# untitled.net
KiCad netlist of a schematic drawn in EAGLE
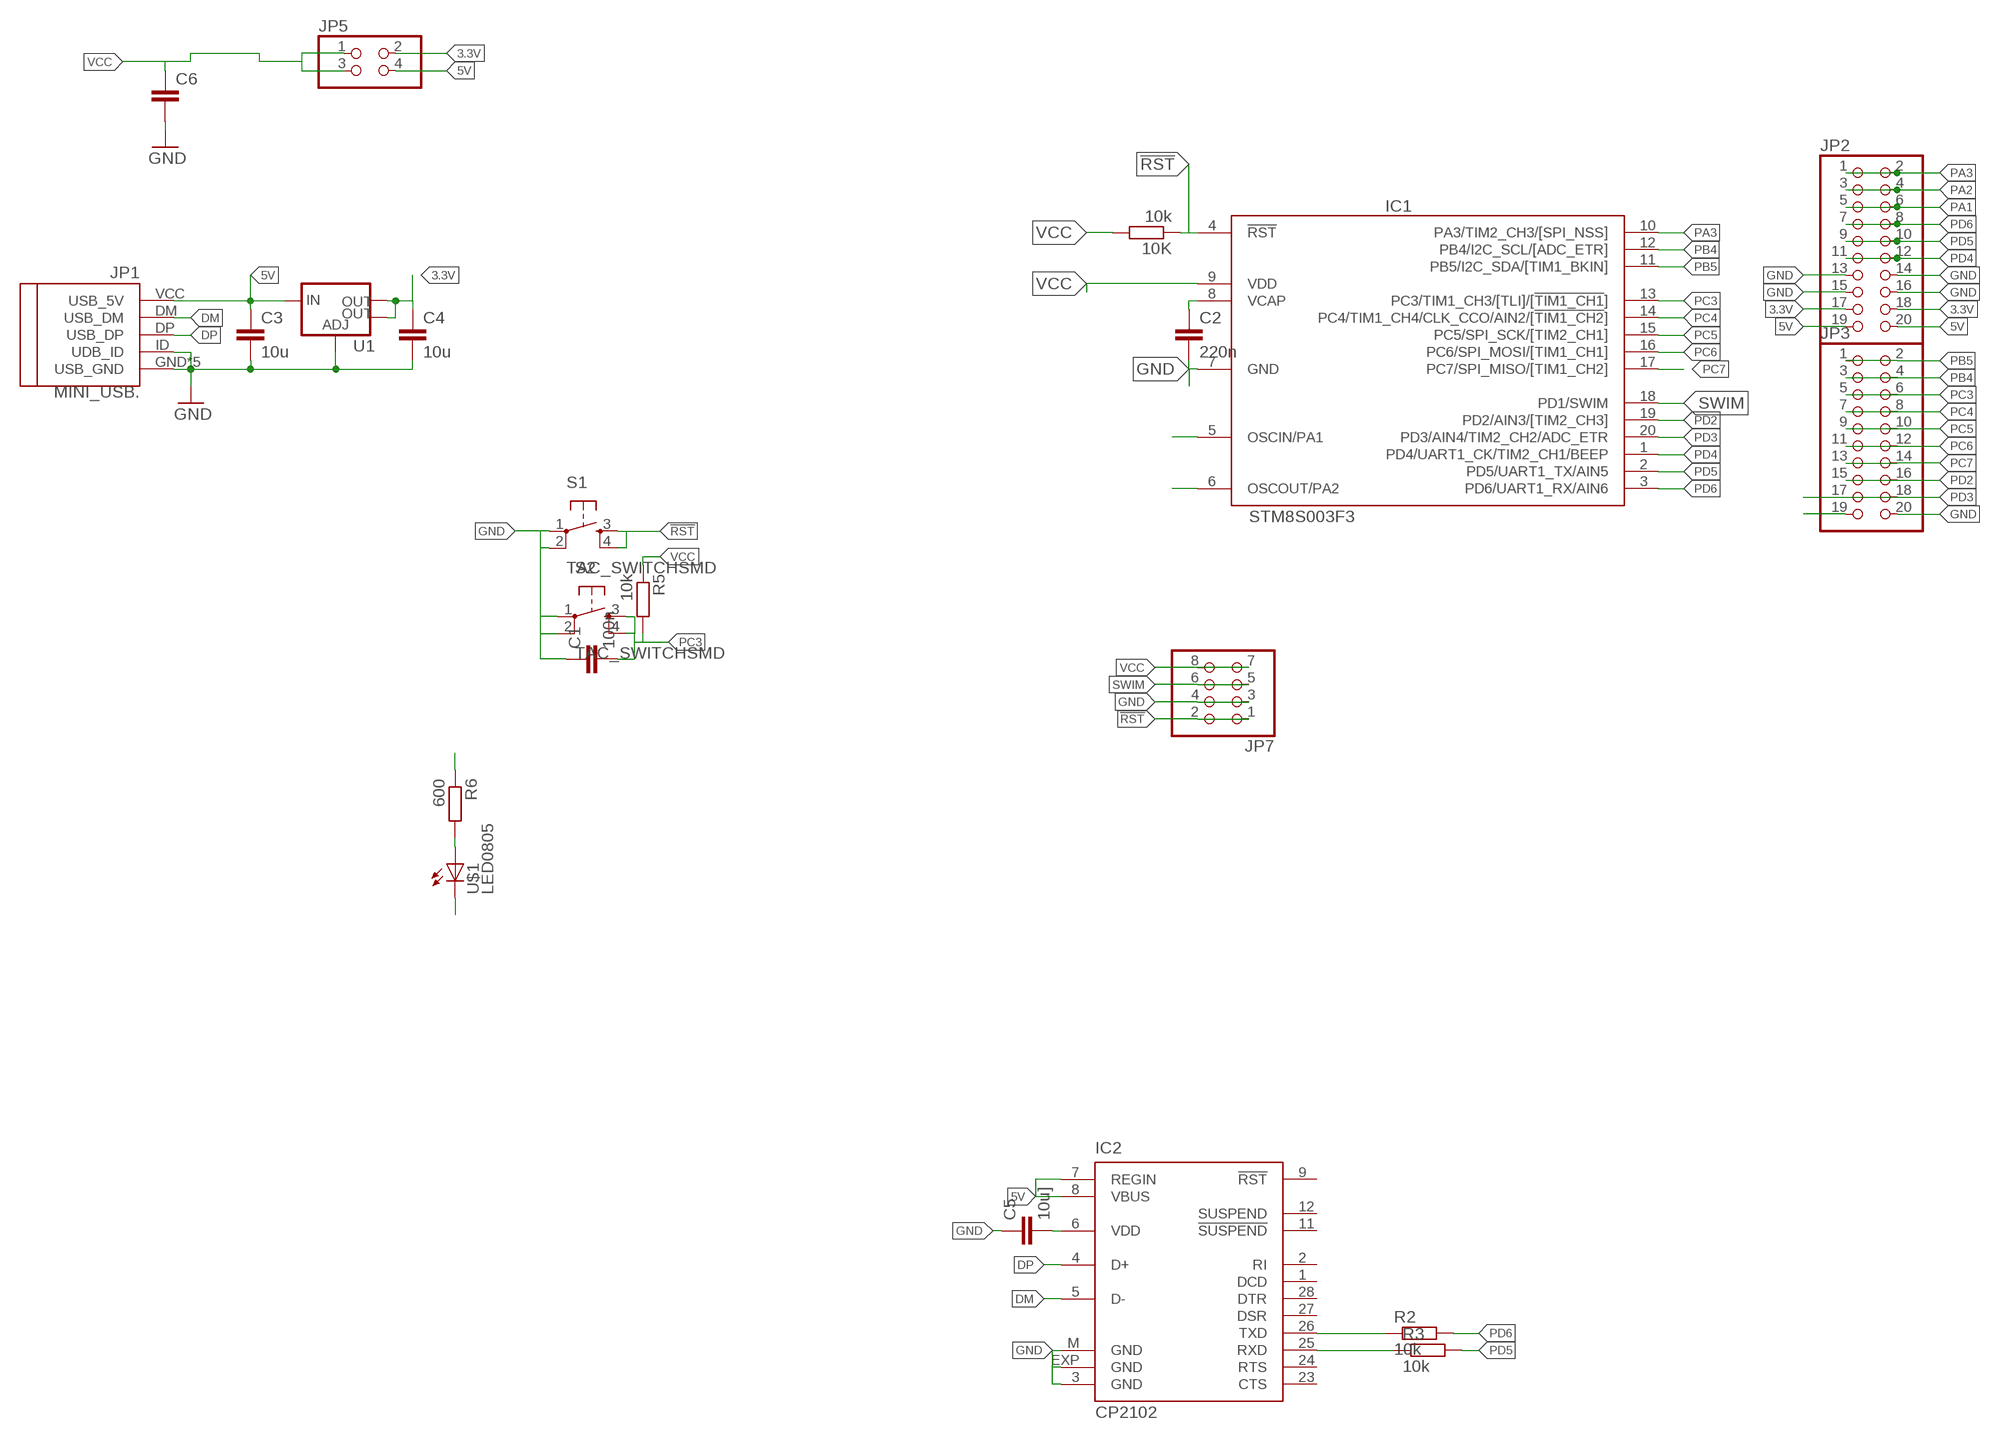
[diagram p0: schematic, sheet 1]

(export (version "E")
  (design (tool "Eeschema 10.0.6"))
  (components
    (comp (ref "10K")
      (value "10k")
      (footprint "eagle-import:0603")
      (libsource (lib "eagle-import") (part "R0603"))
    )
    (comp (ref "C1")
      (value "100n")
      (footprint "eagle-import:C0805")
      (libsource (lib "eagle-import") (part "CC0805"))
    )
    (comp (ref "C2")
      (value "220n")
      (footprint "eagle-import:C0603")
      (libsource (lib "eagle-import") (part "CC0603"))
    )
    (comp (ref "C3")
      (value "10u")
      (footprint "eagle-import:C0805")
      (libsource (lib "eagle-import") (part "CC0805"))
    )
    (comp (ref "C4")
      (value "10u")
      (footprint "eagle-import:C0805")
      (libsource (lib "eagle-import") (part "CC0805"))
    )
    (comp (ref "C5")
      (value "10u]")
      (footprint "eagle-import:C0603")
      (libsource (lib "eagle-import") (part "CC0603"))
    )
    (comp (ref "C6")
      (value "CC0805")
      (footprint "eagle-import:C0805")
      (libsource (lib "eagle-import") (part "CC0805"))
    )
    (comp (ref "IC1")
      (value "STM8S003F3")
      (footprint "eagle-import:TSSOP20")
      (libsource (lib "eagle-import") (part "STM8S003F3"))
    )
    (comp (ref "IC2")
      (value "CP2102")
      (footprint "eagle-import:MLP28")
      (fields (field (name "MF") "FARNELL") (field (name "MPN") "CP2102-GM"))
      (libsource (lib "eagle-import") (part "CP2102"))
    )
    (comp (ref "JP1")
      (value "MINI_USB.")
      (footprint "eagle-import:32005-201")
      (libsource (lib "eagle-import") (part "MINI_USB."))
    )
    (comp (ref "JP2")
      (value "PINHD-2X10_2.54-SMD")
      (footprint "eagle-import:2X10SMD")
      (libsource (lib "eagle-import") (part "PINHD-2X10_2.54-SMD"))
    )
    (comp (ref "JP3")
      (value "PINHD-2X10_2.54-SMD")
      (footprint "eagle-import:2X10SMD")
      (libsource (lib "eagle-import") (part "PINHD-2X10_2.54-SMD"))
    )
    (comp (ref "JP5")
      (value "PINHD-2X02_2.54-SMD")
      (footprint "eagle-import:2X02SMD")
      (libsource (lib "eagle-import") (part "PINHD-2X02_2.54-SMD"))
    )
    (comp (ref "JP7")
      (value "PINHD-2X04_2.54-SMD")
      (footprint "eagle-import:2X04SMD")
      (libsource (lib "eagle-import") (part "PINHD-2X04_2.54-SMD"))
    )
    (comp (ref "R2")
      (value "10k")
      (footprint "eagle-import:0603")
      (libsource (lib "eagle-import") (part "R0603"))
    )
    (comp (ref "R3")
      (value "10k")
      (footprint "eagle-import:0603")
      (libsource (lib "eagle-import") (part "R0603"))
    )
    (comp (ref "R5")
      (value "10k")
      (footprint "eagle-import:0603")
      (libsource (lib "eagle-import") (part "R0603"))
    )
    (comp (ref "R6")
      (value "600")
      (footprint "eagle-import:0603")
      (libsource (lib "eagle-import") (part "R0603"))
    )
    (comp (ref "S1")
      (value "TAC_SWITCHSMD")
      (footprint "eagle-import:TACTILE-SWITCH-SMD")
      (libsource (lib "eagle-import") (part "TAC_SWITCHSMD"))
    )
    (comp (ref "S2")
      (value "TAC_SWITCHSMD")
      (footprint "eagle-import:TACTILE-SWITCH-SMD")
      (libsource (lib "eagle-import") (part "TAC_SWITCHSMD"))
    )
    (comp (ref "U$1")
      (value "LED0805")
      (footprint "eagle-import:0805-LED")
      (libsource (lib "eagle-import") (part "LED0805"))
    )
    (comp (ref "U1")
      (value "V_REG_LM1117SOT223")
      (footprint "eagle-import:SOT223")
      (libsource (lib "eagle-import") (part "V_REG_LM1117SOT223"))
    )
  )
  (nets
    (net (code "1") (name "/~{RST}") (class "Default")
      (node (ref "10K") (pin "1") (pinfunction "1_1") (pintype "passive"))
      (node (ref "IC1") (pin "4") (pinfunction "~{RST}_4") (pintype "input"))
      (node (ref "JP7") (pin "1") (pinfunction "1_1") (pintype "passive"))
      (node (ref "JP7") (pin "2") (pinfunction "2_2") (pintype "passive"))
      (node (ref "S1") (pin "3") (pinfunction "3_3") (pintype "passive"))
      (node (ref "S1") (pin "4") (pinfunction "4_4") (pintype "passive"))
    )
    (net (code "2") (name "3.3V") (class "Default")
      (node (ref "C4") (pin "1") (pinfunction "1_1") (pintype "passive"))
      (node (ref "JP2") (pin "17") (pinfunction "17_17") (pintype "passive"))
      (node (ref "JP2") (pin "18") (pinfunction "18_18") (pintype "passive"))
      (node (ref "JP5") (pin "2") (pinfunction "2_2") (pintype "passive"))
      (node (ref "U1") (pin "2") (pinfunction "OUT_2") (pintype "output"))
      (node (ref "U1") (pin "4") (pinfunction "OUT_4") (pintype "output"))
    )
    (net (code "3") (name "5V") (class "Default")
      (node (ref "C3") (pin "1") (pinfunction "1_1") (pintype "passive"))
      (node (ref "IC2") (pin "7") (pinfunction "REGIN_7") (pintype "passive"))
      (node (ref "IC2") (pin "8") (pinfunction "VBUS_8") (pintype "input"))
      (node (ref "JP1") (pin "VCC") (pinfunction "USB_5V_VCC") (pintype "power_in"))
      (node (ref "JP2") (pin "19") (pinfunction "19_19") (pintype "passive"))
      (node (ref "JP2") (pin "20") (pinfunction "20_20") (pintype "passive"))
      (node (ref "JP5") (pin "4") (pinfunction "4_4") (pintype "passive"))
      (node (ref "U1") (pin "3") (pinfunction "IN_3") (pintype "input"))
    )
    (net (code "4") (name "DM") (class "Default")
      (node (ref "IC2") (pin "5") (pinfunction "D-_5") (pintype "bidirectional"))
      (node (ref "JP1") (pin "DM") (pinfunction "USB_DM_DM") (pintype "bidirectional"))
    )
    (net (code "5") (name "DP") (class "Default")
      (node (ref "IC2") (pin "4") (pinfunction "D+_4") (pintype "bidirectional"))
      (node (ref "JP1") (pin "DP") (pinfunction "USB_DP_DP") (pintype "bidirectional"))
    )
    (net (code "6") (name "GND") (class "Default")
      (node (ref "C1") (pin "1") (pinfunction "1_1") (pintype "passive"))
      (node (ref "C2") (pin "2") (pinfunction "2_2") (pintype "passive"))
      (node (ref "C3") (pin "2") (pinfunction "2_2") (pintype "passive"))
      (node (ref "C4") (pin "2") (pinfunction "2_2") (pintype "passive"))
      (node (ref "C5") (pin "1") (pinfunction "1_1") (pintype "passive"))
      (node (ref "C6") (pin "2") (pinfunction "2_2") (pintype "passive"))
      (node (ref "IC1") (pin "7") (pinfunction "GND_7") (pintype "power_in"))
      (node (ref "IC2") (pin "3") (pinfunction "GND_3") (pintype "power_in"))
      (node (ref "IC2") (pin "EXP") (pinfunction "GND_EXP") (pintype "power_in"))
      (node (ref "IC2") (pin "M") (pinfunction "GND_M") (pintype "power_in"))
      (node (ref "JP1") (pin "GND") (pinfunction "USB_GND_GND") (pintype "power_in"))
      (node (ref "JP1") (pin "ID") (pinfunction "UDB_ID_ID") (pintype "bidirectional"))
      (node (ref "JP1") (pin "M1") (pinfunction "USB_GND_M1") (pintype "power_in"))
      (node (ref "JP1") (pin "M2") (pinfunction "USB_GND_M2") (pintype "power_in"))
      (node (ref "JP1") (pin "M3") (pinfunction "USB_GND_M3") (pintype "power_in"))
      (node (ref "JP1") (pin "M4") (pinfunction "USB_GND_M4") (pintype "power_in"))
      (node (ref "JP2") (pin "13") (pinfunction "13_13") (pintype "passive"))
      (node (ref "JP2") (pin "14") (pinfunction "14_14") (pintype "passive"))
      (node (ref "JP2") (pin "15") (pinfunction "15_15") (pintype "passive"))
      (node (ref "JP2") (pin "16") (pinfunction "16_16") (pintype "passive"))
      (node (ref "JP3") (pin "19") (pinfunction "19_19") (pintype "passive"))
      (node (ref "JP3") (pin "20") (pinfunction "20_20") (pintype "passive"))
      (node (ref "JP7") (pin "3") (pinfunction "3_3") (pintype "passive"))
      (node (ref "JP7") (pin "4") (pinfunction "4_4") (pintype "passive"))
      (node (ref "S1") (pin "1") (pinfunction "1_1") (pintype "passive"))
      (node (ref "S1") (pin "2") (pinfunction "2_2") (pintype "passive"))
      (node (ref "S2") (pin "1") (pinfunction "1_1") (pintype "passive"))
      (node (ref "S2") (pin "2") (pinfunction "2_2") (pintype "passive"))
      (node (ref "U$1") (pin "C") (pinfunction "C_C") (pintype "passive"))
      (node (ref "U1") (pin "1") (pinfunction "ADJ_1") (pintype "input"))
    )
    (net (code "7") (name "Net-(IC1-VCAP)") (class "Default")
      (node (ref "C2") (pin "1") (pinfunction "1_1") (pintype "passive"))
      (node (ref "IC1") (pin "8") (pinfunction "VCAP_8") (pintype "power_in"))
    )
    (net (code "8") (name "Net-(IC2-RXD)") (class "Default")
      (node (ref "IC2") (pin "25") (pinfunction "RXD_25") (pintype "input"))
      (node (ref "R3") (pin "1") (pinfunction "1_1") (pintype "passive"))
    )
    (net (code "9") (name "Net-(IC2-TXD)") (class "Default")
      (node (ref "IC2") (pin "26") (pinfunction "TXD_26") (pintype "output"))
      (node (ref "R2") (pin "1") (pinfunction "1_1") (pintype "passive"))
    )
    (net (code "10") (name "Net-(IC2-VDD)") (class "Default")
      (node (ref "C5") (pin "2") (pinfunction "2_2") (pintype "passive"))
      (node (ref "IC2") (pin "6") (pinfunction "VDD_6") (pintype "power_in"))
    )
    (net (code "11") (name "Net-(R6-Pad2)") (class "Default")
      (node (ref "R6") (pin "2") (pinfunction "2_2") (pintype "passive"))
      (node (ref "U$1") (pin "A") (pinfunction "A_A") (pintype "passive"))
    )
    (net (code "12") (name "PA1") (class "Default")
      (node (ref "IC1") (pin "5") (pinfunction "OSCIN/PA1_5") (pintype "bidirectional"))
      (node (ref "JP2") (pin "5") (pinfunction "5_5") (pintype "passive"))
      (node (ref "JP2") (pin "6") (pinfunction "6_6") (pintype "passive"))
    )
    (net (code "13") (name "PA2") (class "Default")
      (node (ref "IC1") (pin "6") (pinfunction "OSCOUT/PA2_6") (pintype "bidirectional"))
      (node (ref "JP2") (pin "3") (pinfunction "3_3") (pintype "passive"))
      (node (ref "JP2") (pin "4") (pinfunction "4_4") (pintype "passive"))
    )
    (net (code "14") (name "PA3") (class "Default")
      (node (ref "IC1") (pin "10") (pinfunction "PA3/TIM2_CH3/[SPI_NSS]_10") (pintype "bidirectional"))
      (node (ref "JP2") (pin "1") (pinfunction "1_1") (pintype "passive"))
      (node (ref "JP2") (pin "2") (pinfunction "2_2") (pintype "passive"))
    )
    (net (code "15") (name "PB4") (class "Default")
      (node (ref "IC1") (pin "12") (pinfunction "PB4/I2C_SCL/[ADC_ETR]_12") (pintype "bidirectional"))
      (node (ref "JP3") (pin "3") (pinfunction "3_3") (pintype "passive"))
      (node (ref "JP3") (pin "4") (pinfunction "4_4") (pintype "passive"))
    )
    (net (code "16") (name "PB5") (class "Default")
      (node (ref "IC1") (pin "11") (pinfunction "PB5/I2C_SDA/[TIM1_BKIN]_11") (pintype "bidirectional"))
      (node (ref "JP3") (pin "1") (pinfunction "1_1") (pintype "passive"))
      (node (ref "JP3") (pin "2") (pinfunction "2_2") (pintype "passive"))
    )
    (net (code "17") (name "PC3") (class "Default")
      (node (ref "C1") (pin "2") (pinfunction "2_2") (pintype "passive"))
      (node (ref "IC1") (pin "13") (pinfunction "PC3/TIM1_CH3/[TLI]/[~{TIM1_CH1}]_13") (pintype "bidirectional"))
      (node (ref "JP3") (pin "5") (pinfunction "5_5") (pintype "passive"))
      (node (ref "JP3") (pin "6") (pinfunction "6_6") (pintype "passive"))
      (node (ref "R5") (pin "2") (pinfunction "2_2") (pintype "passive"))
      (node (ref "S2") (pin "3") (pinfunction "3_3") (pintype "passive"))
      (node (ref "S2") (pin "4") (pinfunction "4_4") (pintype "passive"))
    )
    (net (code "18") (name "PC4") (class "Default")
      (node (ref "IC1") (pin "14") (pinfunction "PC4/TIM1_CH4/CLK_CCO/AIN2/[~{TIM1_CH2}]_14") (pintype "bidirectional"))
      (node (ref "JP3") (pin "7") (pinfunction "7_7") (pintype "passive"))
      (node (ref "JP3") (pin "8") (pinfunction "8_8") (pintype "passive"))
    )
    (net (code "19") (name "PC5") (class "Default")
      (node (ref "IC1") (pin "15") (pinfunction "PC5/SPI_SCK/[TIM2_CH1]_15") (pintype "bidirectional"))
      (node (ref "JP3") (pin "10") (pinfunction "10_10") (pintype "passive"))
      (node (ref "JP3") (pin "9") (pinfunction "9_9") (pintype "passive"))
    )
    (net (code "20") (name "PC6") (class "Default")
      (node (ref "IC1") (pin "16") (pinfunction "PC6/SPI_MOSI/[TIM1_CH1]_16") (pintype "bidirectional"))
      (node (ref "JP3") (pin "11") (pinfunction "11_11") (pintype "passive"))
      (node (ref "JP3") (pin "12") (pinfunction "12_12") (pintype "passive"))
    )
    (net (code "21") (name "PC7") (class "Default")
      (node (ref "IC1") (pin "17") (pinfunction "PC7/SPI_MISO/[TIM1_CH2]_17") (pintype "bidirectional"))
      (node (ref "JP3") (pin "13") (pinfunction "13_13") (pintype "passive"))
      (node (ref "JP3") (pin "14") (pinfunction "14_14") (pintype "passive"))
    )
    (net (code "22") (name "PD2") (class "Default")
      (node (ref "IC1") (pin "19") (pinfunction "PD2/AIN3/[TIM2_CH3]_19") (pintype "bidirectional"))
      (node (ref "JP3") (pin "15") (pinfunction "15_15") (pintype "passive"))
      (node (ref "JP3") (pin "16") (pinfunction "16_16") (pintype "passive"))
    )
    (net (code "23") (name "PD3") (class "Default")
      (node (ref "IC1") (pin "20") (pinfunction "PD3/AIN4/TIM2_CH2/ADC_ETR_20") (pintype "bidirectional"))
      (node (ref "JP3") (pin "17") (pinfunction "17_17") (pintype "passive"))
      (node (ref "JP3") (pin "18") (pinfunction "18_18") (pintype "passive"))
    )
    (net (code "24") (name "PD4") (class "Default")
      (node (ref "IC1") (pin "1") (pinfunction "PD4/UART1_CK/TIM2_CH1/BEEP_1") (pintype "bidirectional"))
      (node (ref "JP2") (pin "11") (pinfunction "11_11") (pintype "passive"))
      (node (ref "JP2") (pin "12") (pinfunction "12_12") (pintype "passive"))
    )
    (net (code "25") (name "PD5") (class "Default")
      (node (ref "IC1") (pin "2") (pinfunction "PD5/UART1_TX/AIN5_2") (pintype "bidirectional"))
      (node (ref "JP2") (pin "10") (pinfunction "10_10") (pintype "passive"))
      (node (ref "JP2") (pin "9") (pinfunction "9_9") (pintype "passive"))
      (node (ref "R3") (pin "2") (pinfunction "2_2") (pintype "passive"))
    )
    (net (code "26") (name "PD6") (class "Default")
      (node (ref "IC1") (pin "3") (pinfunction "PD6/UART1_RX/AIN6_3") (pintype "bidirectional"))
      (node (ref "JP2") (pin "7") (pinfunction "7_7") (pintype "passive"))
      (node (ref "JP2") (pin "8") (pinfunction "8_8") (pintype "passive"))
      (node (ref "R2") (pin "2") (pinfunction "2_2") (pintype "passive"))
    )
    (net (code "27") (name "SWIM") (class "Default")
      (node (ref "IC1") (pin "18") (pinfunction "PD1/SWIM_18") (pintype "bidirectional"))
      (node (ref "JP7") (pin "5") (pinfunction "5_5") (pintype "passive"))
      (node (ref "JP7") (pin "6") (pinfunction "6_6") (pintype "passive"))
    )
    (net (code "28") (name "VCC") (class "Default")
      (node (ref "10K") (pin "2") (pinfunction "2_2") (pintype "passive"))
      (node (ref "C6") (pin "1") (pinfunction "1_1") (pintype "passive"))
      (node (ref "IC1") (pin "9") (pinfunction "VDD_9") (pintype "power_in"))
      (node (ref "JP5") (pin "1") (pinfunction "1_1") (pintype "passive"))
      (node (ref "JP5") (pin "3") (pinfunction "3_3") (pintype "passive"))
      (node (ref "JP7") (pin "7") (pinfunction "7_7") (pintype "passive"))
      (node (ref "JP7") (pin "8") (pinfunction "8_8") (pintype "passive"))
      (node (ref "R5") (pin "1") (pinfunction "1_1") (pintype "passive"))
      (node (ref "R6") (pin "1") (pinfunction "1_1") (pintype "passive"))
    )
    (net (code "29") (name "unconnected-(IC2-CTS-Pad23)") (class "Default")
      (node (ref "IC2") (pin "23") (pinfunction "CTS_23") (pintype "input"))
    )
    (net (code "30") (name "unconnected-(IC2-DCD-Pad1)") (class "Default")
      (node (ref "IC2") (pin "1") (pinfunction "DCD_1") (pintype "input"))
    )
    (net (code "31") (name "unconnected-(IC2-DSR-Pad27)") (class "Default")
      (node (ref "IC2") (pin "27") (pinfunction "DSR_27") (pintype "input"))
    )
    (net (code "32") (name "unconnected-(IC2-DTR-Pad28)") (class "Default")
      (node (ref "IC2") (pin "28") (pinfunction "DTR_28") (pintype "output"))
    )
    (net (code "33") (name "unconnected-(IC2-RI-Pad2)") (class "Default")
      (node (ref "IC2") (pin "2") (pinfunction "RI_2") (pintype "input"))
    )
    (net (code "34") (name "unconnected-(IC2-RTS-Pad24)") (class "Default")
      (node (ref "IC2") (pin "24") (pinfunction "RTS_24") (pintype "output"))
    )
    (net (code "35") (name "unconnected-(IC2-SUSPEND-Pad12)") (class "Default")
      (node (ref "IC2") (pin "12") (pinfunction "SUSPEND_12") (pintype "output"))
    )
    (net (code "36") (name "unconnected-(IC2-~{RST}-Pad9)") (class "Default")
      (node (ref "IC2") (pin "9") (pinfunction "~{RST}_9") (pintype "bidirectional"))
    )
    (net (code "37") (name "unconnected-(IC2-~{SUSPEND}-Pad11)") (class "Default")
      (node (ref "IC2") (pin "11") (pinfunction "~{SUSPEND}_11") (pintype "output"))
    )
  )
)
